# 10_MHz_Buffer_v1_0.net
KiCad netlist of a schematic drawn in EAGLE
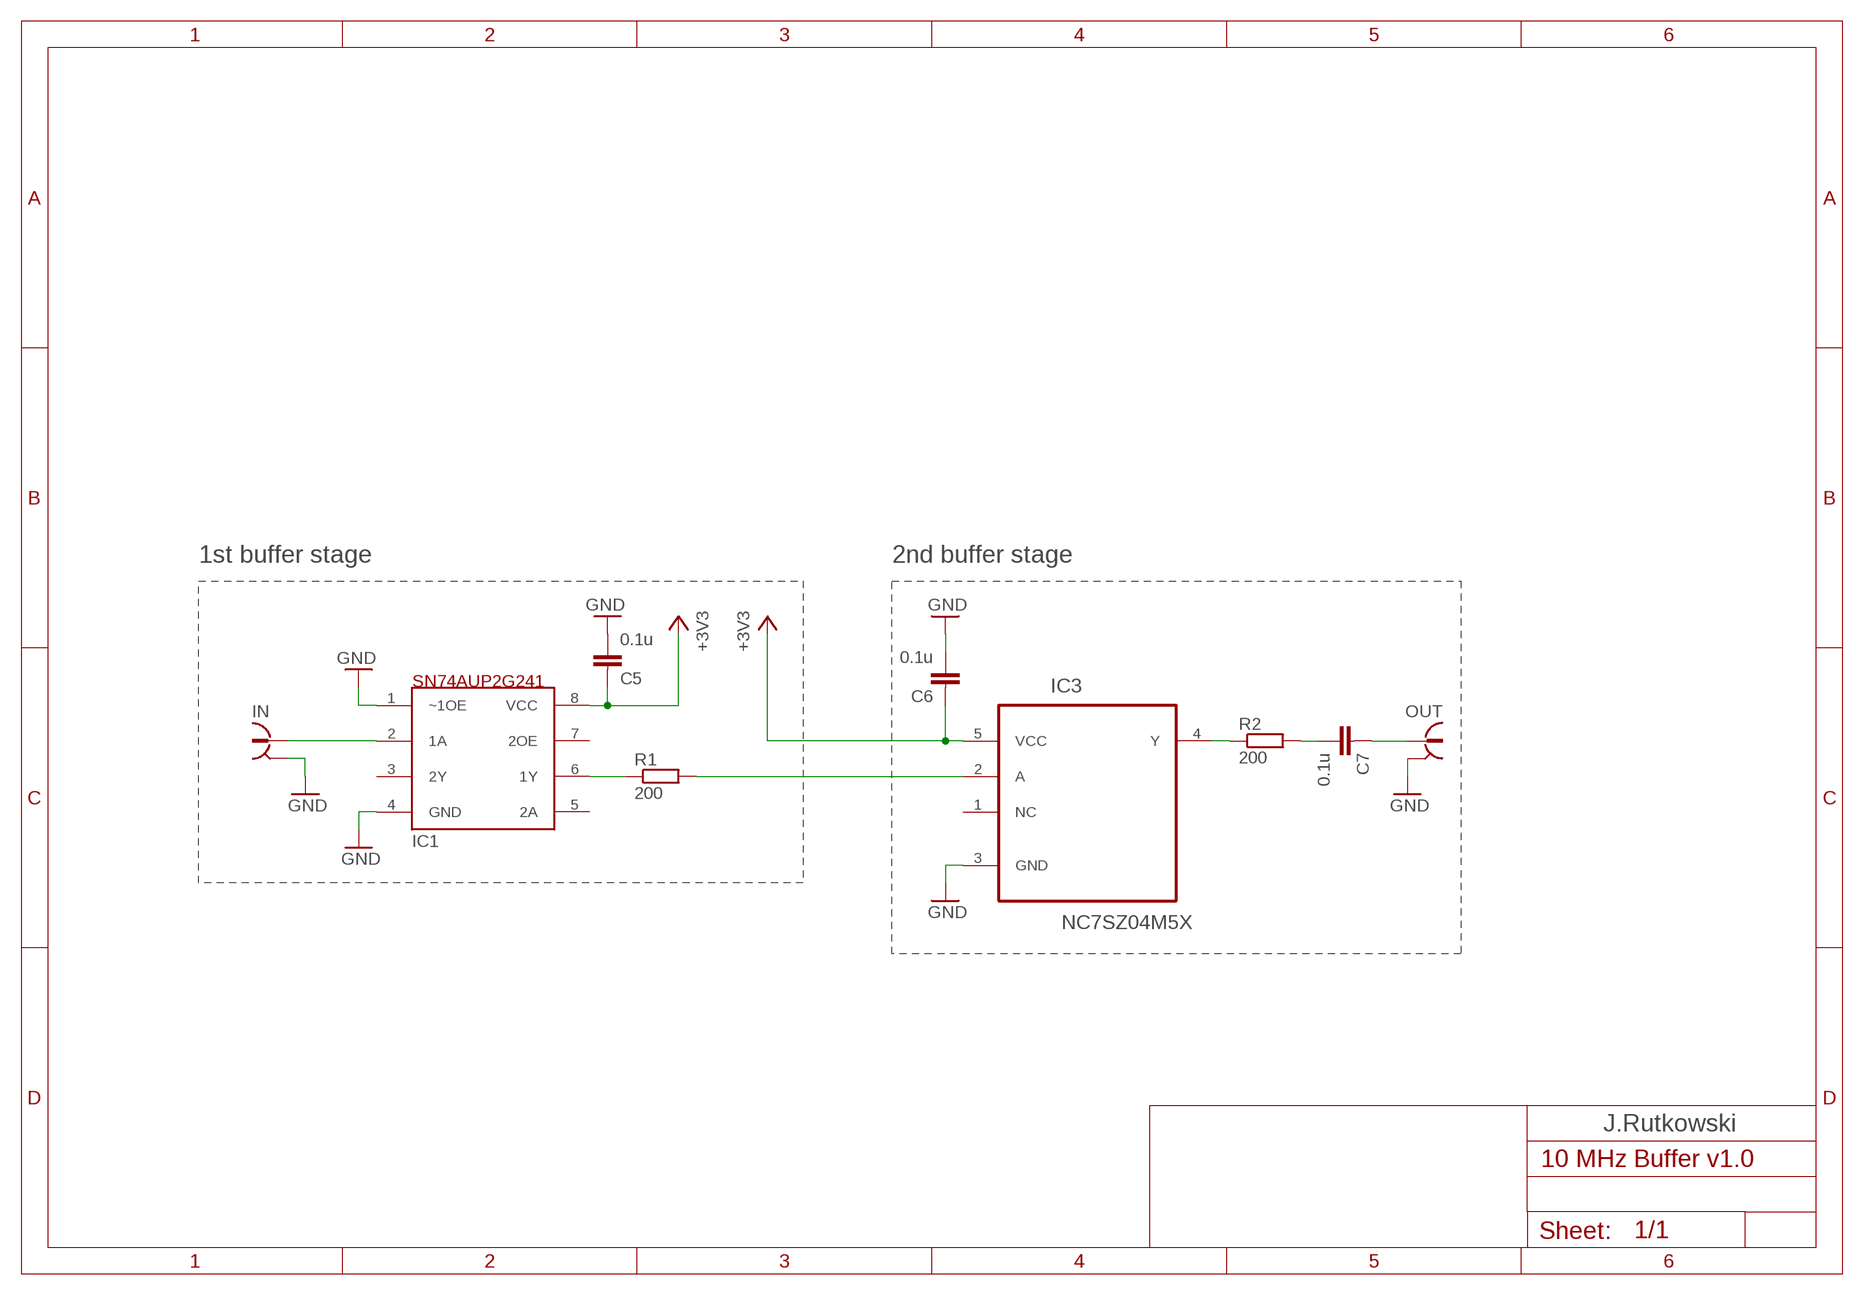
[diagram p0: schematic, sheet 1]

(export (version "E")
  (design (tool "Eeschema 10.0.6"))
  (components
    (comp (ref "C5")
      (value "0.1u")
      (footprint "eagle-import:C0603K")
      (libsource (lib "eagle-import") (part "C-EUC0603K"))
    )
    (comp (ref "C6")
      (value "0.1u")
      (footprint "eagle-import:C0603K")
      (libsource (lib "eagle-import") (part "C-EUC0603K"))
    )
    (comp (ref "C7")
      (value "0.1u")
      (footprint "eagle-import:C0603K")
      (libsource (lib "eagle-import") (part "C-EUC0603K"))
    )
    (comp (ref "IC1")
      (value "SN74AUP2G241")
      (footprint "eagle-import:DCU_(R-PDSO-G8)")
      (libsource (lib "eagle-import") (part "SN74AUP2G241"))
    )
    (comp (ref "IC3")
      (value "NC7SZ04M5X")
      (footprint "eagle-import:SOT95P280X145-5N")
      (libsource (lib "eagle-import") (part "NC7SZ04M5X"))
    )
    (comp (ref "IN")
      (value "734120110")
      (footprint "eagle-import:734120110")
      (libsource (lib "eagle-import") (part "734120110"))
    )
    (comp (ref "OUT")
      (value "734120110")
      (footprint "eagle-import:734120110")
      (libsource (lib "eagle-import") (part "734120110"))
    )
    (comp (ref "R1")
      (value "200")
      (footprint "eagle-import:R0603")
      (libsource (lib "eagle-import") (part "R-EU_R0603"))
    )
    (comp (ref "R2")
      (value "200")
      (footprint "eagle-import:R0603")
      (libsource (lib "eagle-import") (part "R-EU_R0603"))
    )
  )
  (nets
    (net (code "1") (name "+3V3") (class "Default")
      (node (ref "C5") (pin "2") (pinfunction "2_2") (pintype "passive"))
      (node (ref "C6") (pin "2") (pinfunction "2_2") (pintype "passive"))
      (node (ref "IC1") (pin "8") (pinfunction "VCC_8") (pintype "bidirectional"))
      (node (ref "IC3") (pin "5") (pinfunction "VCC_5") (pintype "power_in"))
    )
    (net (code "2") (name "GND") (class "Default")
      (node (ref "C5") (pin "1") (pinfunction "1_1") (pintype "passive"))
      (node (ref "C6") (pin "1") (pinfunction "1_1") (pintype "passive"))
      (node (ref "IC1") (pin "1") (pinfunction "~{1OE}_1") (pintype "bidirectional"))
      (node (ref "IC1") (pin "4") (pinfunction "GND_4") (pintype "bidirectional"))
      (node (ref "IC3") (pin "3") (pinfunction "GND_3") (pintype "passive"))
      (node (ref "IN") (pin "S@1") (pinfunction "2_S@1") (pintype "passive"))
      (node (ref "IN") (pin "S@2") (pinfunction "2_S@2") (pintype "passive"))
      (node (ref "IN") (pin "S@3") (pinfunction "2_S@3") (pintype "passive"))
      (node (ref "OUT") (pin "S@1") (pinfunction "2_S@1") (pintype "passive"))
      (node (ref "OUT") (pin "S@2") (pinfunction "2_S@2") (pintype "passive"))
      (node (ref "OUT") (pin "S@3") (pinfunction "2_S@3") (pintype "passive"))
    )
    (net (code "3") (name "Net-(C7-Pad1)") (class "Default")
      (node (ref "C7") (pin "1") (pinfunction "1_1") (pintype "passive"))
      (node (ref "R2") (pin "2") (pinfunction "2_2") (pintype "passive"))
    )
    (net (code "4") (name "Net-(C7-Pad2)") (class "Default")
      (node (ref "C7") (pin "2") (pinfunction "2_2") (pintype "passive"))
      (node (ref "OUT") (pin "1") (pinfunction "1_1") (pintype "passive"))
    )
    (net (code "5") (name "Net-(IC1-1A)") (class "Default")
      (node (ref "IC1") (pin "2") (pinfunction "1A_2") (pintype "bidirectional"))
      (node (ref "IN") (pin "1") (pinfunction "1_1") (pintype "passive"))
    )
    (net (code "6") (name "Net-(IC1-1Y)") (class "Default")
      (node (ref "IC1") (pin "6") (pinfunction "1Y_6") (pintype "bidirectional"))
      (node (ref "R1") (pin "1") (pinfunction "1_1") (pintype "passive"))
    )
    (net (code "7") (name "Net-(IC3-A)") (class "Default")
      (node (ref "IC3") (pin "2") (pinfunction "A_2") (pintype "input"))
      (node (ref "R1") (pin "2") (pinfunction "2_2") (pintype "passive"))
    )
    (net (code "8") (name "Net-(IC3-Y)") (class "Default")
      (node (ref "IC3") (pin "4") (pinfunction "Y_4") (pintype "output"))
      (node (ref "R2") (pin "1") (pinfunction "1_1") (pintype "passive"))
    )
    (net (code "9") (name "unconnected-(IC1-2A-Pad5)") (class "Default")
      (node (ref "IC1") (pin "5") (pinfunction "2A_5") (pintype "bidirectional"))
    )
    (net (code "10") (name "unconnected-(IC1-2OE-Pad7)") (class "Default")
      (node (ref "IC1") (pin "7") (pinfunction "2OE_7") (pintype "bidirectional"))
    )
    (net (code "11") (name "unconnected-(IC1-2Y-Pad3)") (class "Default")
      (node (ref "IC1") (pin "3") (pinfunction "2Y_3") (pintype "bidirectional"))
    )
    (net (code "12") (name "unconnected-(IC3-NC-Pad1)") (class "Default")
      (node (ref "IC3") (pin "1") (pinfunction "NC_1") (pintype "no_connect"))
    )
  )
)
